# BW1098OBC_Connector.net
KiCad netlist of a schematic drawn in Altium Designer
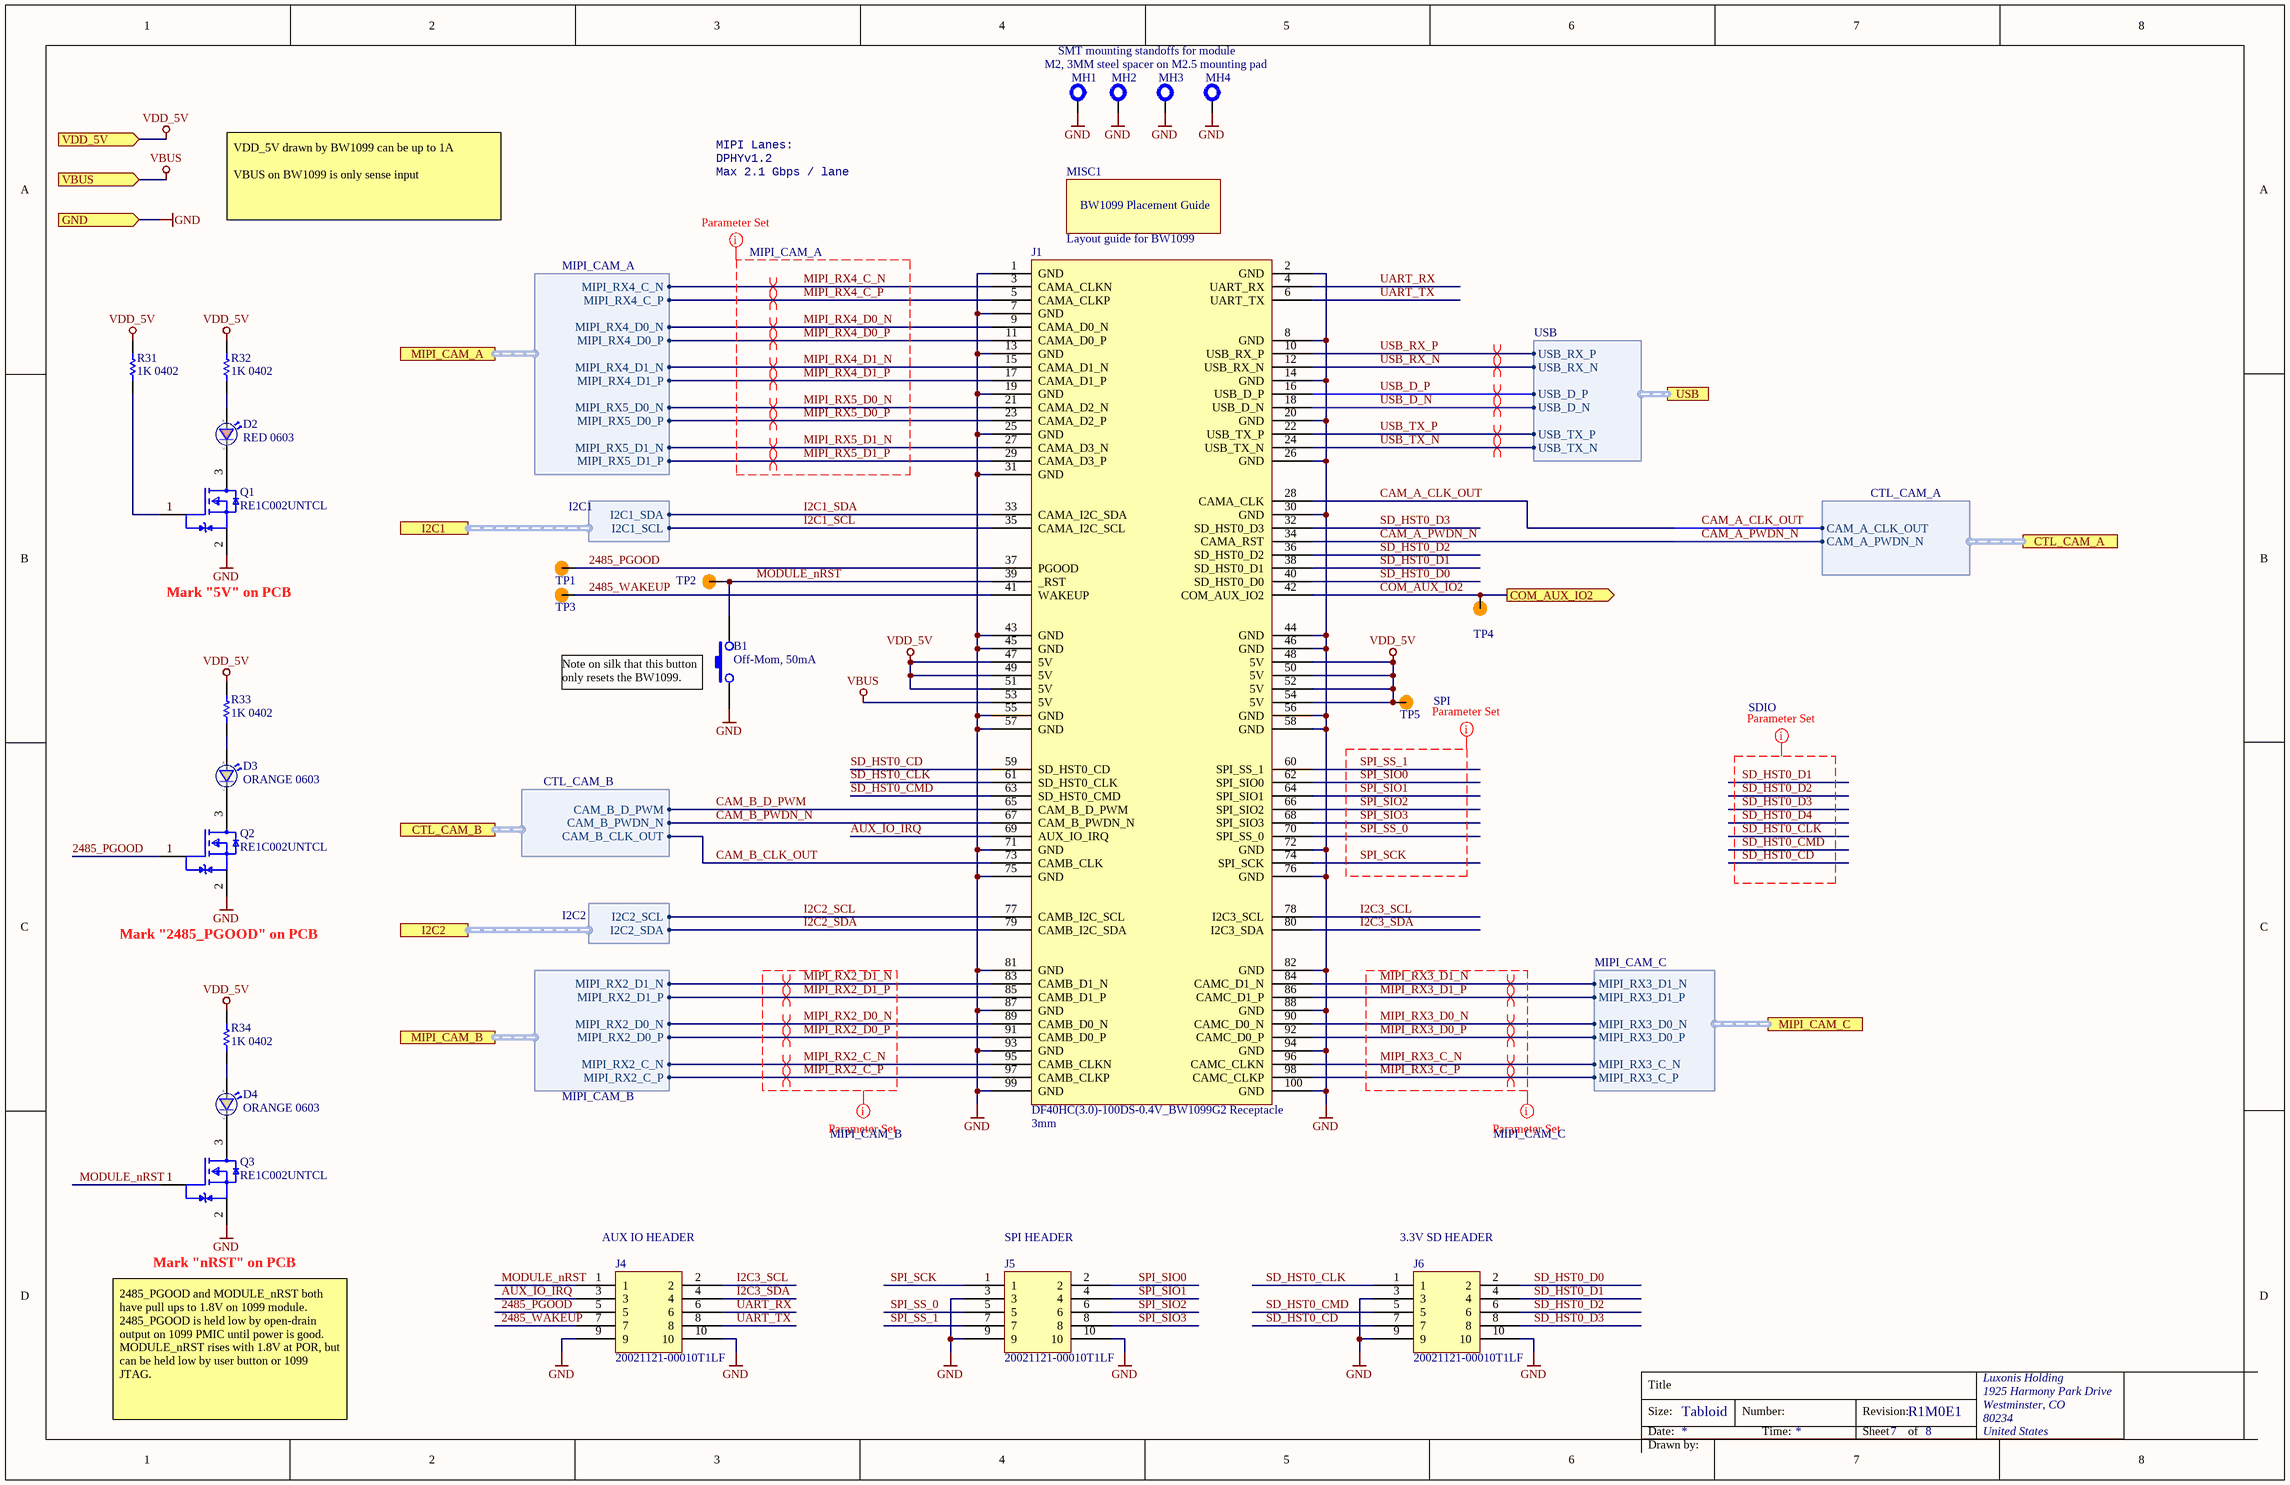
[diagram p0: BW1098OBC_Connector.SchDoc]

(export (version "E")
  (design (tool "Eeschema 10.0.6"))
  (components
    (comp (ref "B1")
      (value "Off-Mom, 50mA")
      (footprint "LuxonisMaster:DTSM-32N-V")
      (description "SWITCH TACTILE SMT 3.5mm * 6mm , brown 160gf")
      (libsource (lib "LuxonisMaster") (part "DTSM-32N-V"))
    )
    (comp (ref "D2")
      (value "RED 0603")
      (footprint "LuxonisMaster:SML_D1xx8W")
      (description "LED RED DIFFUSED 0603 SMD Red 620nm LED Indication - Discrete 2.2V 0603 (1608 Metric)")
      (libsource (lib "LuxonisMaster") (part "SML-D12U8WT86"))
    )
    (comp (ref "D3")
      (value "ORANGE 0603")
      (footprint "LuxonisMaster:SML_D1xx8W")
      (description "LED ORANGE DIFFUSED 0603 SMD Orange 605nm LED Indication - Discrete 2.2V 0603 (1608 Metric)")
      (libsource (lib "LuxonisMaster") (part "SML-D12D8WT86"))
    )
    (comp (ref "D4")
      (value "ORANGE 0603")
      (footprint "LuxonisMaster:SML_D1xx8W")
      (description "LED ORANGE DIFFUSED 0603 SMD Orange 605nm LED Indication - Discrete 2.2V 0603 (1608 Metric)")
      (libsource (lib "LuxonisMaster") (part "SML-D12D8WT86"))
    )
    (comp (ref "J1")
      (value "DF40HC(3.0)-100DS-0.4V_BW1099G2 Receptacle")
      (footprint "LuxonisMaster:DF40HC-3.0-100DS-0.4V_minpad")
      (description "CONN RCPT 100POS 0.4MM SMD GOLD")
      (fields (field (name "MATED STACKING HEIGHT") "3mm"))
      (libsource (lib "LuxonisMaster") (part "DF40HC(3.0)-100DS-0.4V_BW1099_G2"))
    )
    (comp (ref "J4")
      (value "20021121-00010T1LF")
      (footprint "BW1098OBC:20021121-00010T1LF")
      (description "CONN HEADER SMD 10POS 1.27MM")
      (libsource (lib "BW1098OBC") (part "20021121-00010T1LF"))
    )
    (comp (ref "J5")
      (value "20021121-00010T1LF")
      (footprint "BW1098OBC:20021121-00010T1LF")
      (description "CONN HEADER SMD 10POS 1.27MM")
      (libsource (lib "BW1098OBC") (part "20021121-00010T1LF"))
    )
    (comp (ref "J6")
      (value "20021121-00010T1LF")
      (footprint "BW1098OBC:20021121-00010T1LF")
      (description "CONN HEADER SMD 10POS 1.27MM")
      (libsource (lib "BW1098OBC") (part "20021121-00010T1LF"))
    )
    (comp (ref "MH1")
      (value "M2, 3MM steel spacer on M2.5 mounting pad")
      (footprint "LuxonisMaster:9774030243R")
      (description "MP ROUND STANDOFF M2X0.4 STEEL 3MM")
      (libsource (lib "LuxonisMaster") (part "9774030243R"))
    )
    (comp (ref "MH2")
      (value "M2, 3MM steel spacer on M2.5 mounting pad")
      (footprint "LuxonisMaster:9774030243R")
      (description "MP ROUND STANDOFF M2X0.4 STEEL 3MM")
      (libsource (lib "LuxonisMaster") (part "9774030243R"))
    )
    (comp (ref "MH3")
      (value "M2, 3MM steel spacer on M2.5 mounting pad")
      (footprint "LuxonisMaster:9774030243R")
      (description "MP ROUND STANDOFF M2X0.4 STEEL 3MM")
      (libsource (lib "LuxonisMaster") (part "9774030243R"))
    )
    (comp (ref "MH4")
      (value "M2, 3MM steel spacer on M2.5 mounting pad")
      (footprint "LuxonisMaster:9774030243R")
      (description "MP ROUND STANDOFF M2X0.4 STEEL 3MM")
      (libsource (lib "LuxonisMaster") (part "9774030243R"))
    )
    (comp (ref "MISC1")
      (value "Layout guide for BW1099")
      (footprint "LuxonisMaster:BW1099_Footprint")
      (description "MISC - Use for aligning BW1099 mount")
      (libsource (lib "LuxonisMaster") (part "BW1099_Footprint"))
    )
    (comp (ref "Q1")
      (value "RE1C002UNTCL")
      (footprint "LuxonisMaster:RE1C002UNTCL")
      (description "MOSFET N-CH 20V 0.2A EMT3")
      (libsource (lib "LuxonisMaster") (part "RE1C002UNTCL"))
    )
    (comp (ref "Q2")
      (value "RE1C002UNTCL")
      (footprint "LuxonisMaster:RE1C002UNTCL")
      (description "MOSFET N-CH 20V 0.2A EMT3")
      (libsource (lib "LuxonisMaster") (part "RE1C002UNTCL"))
    )
    (comp (ref "Q3")
      (value "RE1C002UNTCL")
      (footprint "LuxonisMaster:RE1C002UNTCL")
      (description "MOSFET N-CH 20V 0.2A EMT3")
      (libsource (lib "LuxonisMaster") (part "RE1C002UNTCL"))
    )
    (comp (ref "R31")
      (value "1K 0402")
      (footprint "RES_Altium_Vault_Generic:RESC0402(1005)_L")
      (fields (field (name "TOLERANCE") "1%"))
      (libsource (lib "LuxonisMaster") (part "RC0402FR-071KL"))
    )
    (comp (ref "R32")
      (value "1K 0402")
      (footprint "RES_Altium_Vault_Generic:RESC0402(1005)_L")
      (fields (field (name "TOLERANCE") "1%"))
      (libsource (lib "LuxonisMaster") (part "RC0402FR-071KL"))
    )
    (comp (ref "R33")
      (value "1K 0402")
      (footprint "RES_Altium_Vault_Generic:RESC0402(1005)_L")
      (fields (field (name "TOLERANCE") "1%"))
      (libsource (lib "LuxonisMaster") (part "RC0402FR-071KL"))
    )
    (comp (ref "R34")
      (value "1K 0402")
      (footprint "RES_Altium_Vault_Generic:RESC0402(1005)_L")
      (fields (field (name "TOLERANCE") "1%"))
      (libsource (lib "LuxonisMaster") (part "RC0402FR-071KL"))
    )
    (comp (ref "TP1")
      (value "TP100_200_NS")
      (footprint "LuxonisMaster:TP100_200_NS")
      (libsource (lib "LuxonisMaster") (part "TEST_POINT"))
    )
    (comp (ref "TP2")
      (value "TP100_200_NS")
      (footprint "LuxonisMaster:TP100_200_NS")
      (libsource (lib "LuxonisMaster") (part "TEST_POINT"))
    )
    (comp (ref "TP3")
      (value "TP100_200_NS")
      (footprint "LuxonisMaster:TP100_200_NS")
      (libsource (lib "LuxonisMaster") (part "TEST_POINT"))
    )
    (comp (ref "TP4")
      (value "TP100_200_NS")
      (footprint "LuxonisMaster:TP100_200_NS")
      (libsource (lib "LuxonisMaster") (part "TEST_POINT"))
    )
    (comp (ref "TP5")
      (value "TP100_200_NS")
      (footprint "LuxonisMaster:TP100_200_NS")
      (libsource (lib "LuxonisMaster") (part "TEST_POINT"))
    )
  )
  (nets
    (net (code "9") (name "/2485_PGOOD") (class "Default")
      (node (ref "J1") (pin "37") (pinfunction "PGOOD_37") (pintype "passive"))
      (node (ref "J4") (pin "5") (pinfunction "5_5") (pintype "passive"))
      (node (ref "Q2") (pin "1") (pinfunction "Gate_1") (pintype "passive"))
      (node (ref "TP1") (pin "1") (pintype "passive"))
    )
    (net (code "10") (name "/2485_WAKEUP") (class "Default")
      (node (ref "J1") (pin "41") (pinfunction "WAKEUP_41") (pintype "passive"))
      (node (ref "J4") (pin "7") (pinfunction "7_7") (pintype "passive"))
      (node (ref "TP3") (pin "1") (pintype "passive"))
    )
    (net (code "11") (name "/AUX_IO_IRQ") (class "Default")
      (node (ref "J1") (pin "69") (pinfunction "AUX_IO_IRQ_69") (pintype "passive"))
      (node (ref "J4") (pin "3") (pinfunction "3_3") (pintype "passive"))
    )
    (net (code "12") (name "/CAM_A_CLK_OUT") (class "Default")
      (node (ref "J1") (pin "28") (pinfunction "CAMA_CLK_28") (pintype "passive"))
    )
    (net (code "13") (name "/CAM_A_PWDN_N") (class "Default")
      (node (ref "J1") (pin "34") (pinfunction "CAMA_RST_34") (pintype "passive"))
    )
    (net (code "14") (name "/CAM_B_CLK_OUT") (class "Default")
      (node (ref "J1") (pin "73") (pinfunction "CAMB_CLK_73") (pintype "passive"))
    )
    (net (code "15") (name "/CAM_B_D_PWM") (class "Default")
      (node (ref "J1") (pin "65") (pinfunction "CAM_B_D_PWM_65") (pintype "passive"))
    )
    (net (code "16") (name "/CAM_B_PWDN_N") (class "Default")
      (node (ref "J1") (pin "67") (pinfunction "CAM_B_PWDN_N_67") (pintype "passive"))
    )
    (net (code "17") (name "/COM_AUX_IO2") (class "Default")
      (node (ref "J1") (pin "42") (pinfunction "COM_AUX_IO2_42") (pintype "passive"))
      (node (ref "TP4") (pin "1") (pintype "passive"))
    )
    (net (code "18") (name "/I2C1_SCL") (class "Default")
      (node (ref "J1") (pin "35") (pinfunction "CAMA_I2C_SCL_35") (pintype "passive"))
    )
    (net (code "19") (name "/I2C1_SDA") (class "Default")
      (node (ref "J1") (pin "33") (pinfunction "CAMA_I2C_SDA_33") (pintype "passive"))
    )
    (net (code "20") (name "/I2C2_SCL") (class "Default")
      (node (ref "J1") (pin "77") (pinfunction "CAMB_I2C_SCL_77") (pintype "passive"))
    )
    (net (code "21") (name "/I2C2_SDA") (class "Default")
      (node (ref "J1") (pin "79") (pinfunction "CAMB_I2C_SDA_79") (pintype "passive"))
    )
    (net (code "22") (name "/I2C3_SCL") (class "Default")
      (node (ref "J1") (pin "78") (pinfunction "I2C3_SCL_78") (pintype "passive"))
      (node (ref "J4") (pin "2") (pinfunction "2_2") (pintype "passive"))
    )
    (net (code "23") (name "/I2C3_SDA") (class "Default")
      (node (ref "J1") (pin "80") (pinfunction "I2C3_SDA_80") (pintype "passive"))
      (node (ref "J4") (pin "4") (pinfunction "4_4") (pintype "passive"))
    )
    (net (code "24") (name "/MIPI_RX2_C_N") (class "Default")
      (node (ref "J1") (pin "95") (pinfunction "CAMB_CLKN_95") (pintype "passive"))
    )
    (net (code "25") (name "/MIPI_RX2_C_P") (class "Default")
      (node (ref "J1") (pin "97") (pinfunction "CAMB_CLKP_97") (pintype "passive"))
    )
    (net (code "26") (name "/MIPI_RX2_D0_N") (class "Default")
      (node (ref "J1") (pin "89") (pinfunction "CAMB_D0_N_89") (pintype "passive"))
    )
    (net (code "27") (name "/MIPI_RX2_D0_P") (class "Default")
      (node (ref "J1") (pin "91") (pinfunction "CAMB_D0_P_91") (pintype "passive"))
    )
    (net (code "28") (name "/MIPI_RX2_D1_N") (class "Default")
      (node (ref "J1") (pin "83") (pinfunction "CAMB_D1_N_83") (pintype "passive"))
    )
    (net (code "29") (name "/MIPI_RX2_D1_P") (class "Default")
      (node (ref "J1") (pin "85") (pinfunction "CAMB_D1_P_85") (pintype "passive"))
    )
    (net (code "30") (name "/MIPI_RX3_C_N") (class "Default")
      (node (ref "J1") (pin "96") (pinfunction "CAMC_CLKN_96") (pintype "passive"))
    )
    (net (code "31") (name "/MIPI_RX3_C_P") (class "Default")
      (node (ref "J1") (pin "98") (pinfunction "CAMC_CLKP_98") (pintype "passive"))
    )
    (net (code "32") (name "/MIPI_RX3_D0_N") (class "Default")
      (node (ref "J1") (pin "90") (pinfunction "CAMC_D0_N_90") (pintype "passive"))
    )
    (net (code "33") (name "/MIPI_RX3_D0_P") (class "Default")
      (node (ref "J1") (pin "92") (pinfunction "CAMC_D0_P_92") (pintype "passive"))
    )
    (net (code "34") (name "/MIPI_RX3_D1_N") (class "Default")
      (node (ref "J1") (pin "84") (pinfunction "CAMC_D1_N_84") (pintype "passive"))
    )
    (net (code "35") (name "/MIPI_RX3_D1_P") (class "Default")
      (node (ref "J1") (pin "86") (pinfunction "CAMC_D1_P_86") (pintype "passive"))
    )
    (net (code "36") (name "/MIPI_RX4_C_N") (class "Default")
      (node (ref "J1") (pin "3") (pinfunction "CAMA_CLKN_3") (pintype "passive"))
    )
    (net (code "37") (name "/MIPI_RX4_C_P") (class "Default")
      (node (ref "J1") (pin "5") (pinfunction "CAMA_CLKP_5") (pintype "passive"))
    )
    (net (code "38") (name "/MIPI_RX4_D0_N") (class "Default")
      (node (ref "J1") (pin "9") (pinfunction "CAMA_D0_N_9") (pintype "passive"))
    )
    (net (code "39") (name "/MIPI_RX4_D0_P") (class "Default")
      (node (ref "J1") (pin "11") (pinfunction "CAMA_D0_P_11") (pintype "passive"))
    )
    (net (code "40") (name "/MIPI_RX4_D1_N") (class "Default")
      (node (ref "J1") (pin "15") (pinfunction "CAMA_D1_N_15") (pintype "passive"))
    )
    (net (code "41") (name "/MIPI_RX4_D1_P") (class "Default")
      (node (ref "J1") (pin "17") (pinfunction "CAMA_D1_P_17") (pintype "passive"))
    )
    (net (code "42") (name "/MIPI_RX5_D0_N") (class "Default")
      (node (ref "J1") (pin "21") (pinfunction "CAMA_D2_N_21") (pintype "passive"))
    )
    (net (code "43") (name "/MIPI_RX5_D0_P") (class "Default")
      (node (ref "J1") (pin "23") (pinfunction "CAMA_D2_P_23") (pintype "passive"))
    )
    (net (code "44") (name "/MIPI_RX5_D1_N") (class "Default")
      (node (ref "J1") (pin "27") (pinfunction "CAMA_D3_N_27") (pintype "passive"))
    )
    (net (code "45") (name "/MIPI_RX5_D1_P") (class "Default")
      (node (ref "J1") (pin "29") (pinfunction "CAMA_D3_P_29") (pintype "passive"))
    )
    (net (code "46") (name "/MODULE_nRST") (class "Default")
      (node (ref "B1") (pin "2") (pinfunction "2_2") (pintype "passive"))
      (node (ref "J1") (pin "39") (pinfunction "_RST_39") (pintype "passive"))
      (node (ref "J4") (pin "1") (pinfunction "1_1") (pintype "passive"))
      (node (ref "Q3") (pin "1") (pinfunction "Gate_1") (pintype "passive"))
      (node (ref "TP2") (pin "1") (pintype "passive"))
    )
    (net (code "47") (name "/SD_HST0_CD") (class "Default")
      (node (ref "J1") (pin "59") (pinfunction "SD_HST0_CD_59") (pintype "passive"))
      (node (ref "J6") (pin "7") (pinfunction "7_7") (pintype "passive"))
    )
    (net (code "48") (name "/SD_HST0_CLK") (class "Default")
      (node (ref "J1") (pin "61") (pinfunction "SD_HST0_CLK_61") (pintype "passive"))
      (node (ref "J6") (pin "1") (pinfunction "1_1") (pintype "passive"))
    )
    (net (code "49") (name "/SD_HST0_CMD") (class "Default")
      (node (ref "J1") (pin "63") (pinfunction "SD_HST0_CMD_63") (pintype "passive"))
      (node (ref "J6") (pin "5") (pinfunction "5_5") (pintype "passive"))
    )
    (net (code "50") (name "/SD_HST0_D0") (class "Default")
      (node (ref "J1") (pin "40") (pinfunction "SD_HST0_D0_40") (pintype "passive"))
      (node (ref "J6") (pin "2") (pinfunction "2_2") (pintype "passive"))
    )
    (net (code "51") (name "/SD_HST0_D1") (class "Default")
      (node (ref "J1") (pin "38") (pinfunction "SD_HST0_D1_38") (pintype "passive"))
      (node (ref "J6") (pin "4") (pinfunction "4_4") (pintype "passive"))
    )
    (net (code "52") (name "/SD_HST0_D2") (class "Default")
      (node (ref "J1") (pin "36") (pinfunction "SD_HST0_D2_36") (pintype "passive"))
      (node (ref "J6") (pin "6") (pinfunction "6_6") (pintype "passive"))
    )
    (net (code "53") (name "/SD_HST0_D3") (class "Default")
      (node (ref "J1") (pin "32") (pinfunction "SD_HST0_D3_32") (pintype "passive"))
      (node (ref "J6") (pin "8") (pinfunction "8_8") (pintype "passive"))
    )
    (net (code "55") (name "/SPI_SCK") (class "Default")
      (node (ref "J1") (pin "74") (pinfunction "SPI_SCK_74") (pintype "passive"))
      (node (ref "J5") (pin "1") (pinfunction "1_1") (pintype "passive"))
    )
    (net (code "56") (name "/SPI_SIO0") (class "Default")
      (node (ref "J1") (pin "62") (pinfunction "SPI_SIO0_62") (pintype "passive"))
      (node (ref "J5") (pin "2") (pinfunction "2_2") (pintype "passive"))
    )
    (net (code "57") (name "/SPI_SIO1") (class "Default")
      (node (ref "J1") (pin "64") (pinfunction "SPI_SIO1_64") (pintype "passive"))
      (node (ref "J5") (pin "4") (pinfunction "4_4") (pintype "passive"))
    )
    (net (code "58") (name "/SPI_SIO2") (class "Default")
      (node (ref "J1") (pin "66") (pinfunction "SPI_SIO2_66") (pintype "passive"))
      (node (ref "J5") (pin "6") (pinfunction "6_6") (pintype "passive"))
    )
    (net (code "59") (name "/SPI_SIO3") (class "Default")
      (node (ref "J1") (pin "68") (pinfunction "SPI_SIO3_68") (pintype "passive"))
      (node (ref "J5") (pin "8") (pinfunction "8_8") (pintype "passive"))
    )
    (net (code "60") (name "/SPI_SS_0") (class "Default")
      (node (ref "J1") (pin "70") (pinfunction "SPI_SS_0_70") (pintype "passive"))
      (node (ref "J5") (pin "5") (pinfunction "5_5") (pintype "passive"))
    )
    (net (code "61") (name "/SPI_SS_1") (class "Default")
      (node (ref "J1") (pin "60") (pinfunction "SPI_SS_1_60") (pintype "passive"))
      (node (ref "J5") (pin "7") (pinfunction "7_7") (pintype "passive"))
    )
    (net (code "62") (name "/UART_RX") (class "Default")
      (node (ref "J1") (pin "4") (pinfunction "UART_RX_4") (pintype "passive"))
      (node (ref "J4") (pin "6") (pinfunction "6_6") (pintype "passive"))
    )
    (net (code "63") (name "/UART_TX") (class "Default")
      (node (ref "J1") (pin "6") (pinfunction "UART_TX_6") (pintype "passive"))
      (node (ref "J4") (pin "8") (pinfunction "8_8") (pintype "passive"))
    )
    (net (code "64") (name "/USB_D_N") (class "Default")
      (node (ref "J1") (pin "18") (pinfunction "USB_D_N_18") (pintype "passive"))
    )
    (net (code "65") (name "/USB_D_P") (class "Default")
      (node (ref "J1") (pin "16") (pinfunction "USB_D_P_16") (pintype "passive"))
    )
    (net (code "66") (name "/USB_RX_N") (class "Default")
      (node (ref "J1") (pin "12") (pinfunction "USB_RX_N_12") (pintype "passive"))
    )
    (net (code "67") (name "/USB_RX_P") (class "Default")
      (node (ref "J1") (pin "10") (pinfunction "USB_RX_P_10") (pintype "passive"))
    )
    (net (code "68") (name "/USB_TX_N") (class "Default")
      (node (ref "J1") (pin "24") (pinfunction "USB_TX_N_24") (pintype "passive"))
    )
    (net (code "69") (name "/USB_TX_P") (class "Default")
      (node (ref "J1") (pin "22") (pinfunction "USB_TX_P_22") (pintype "passive"))
    )
    (net (code "78") (name "GND") (class "Default")
      (node (ref "B1") (pin "1") (pinfunction "1_1") (pintype "passive"))
      (node (ref "J1") (pin "1") (pinfunction "GND_1") (pintype "passive"))
      (node (ref "J1") (pin "100") (pinfunction "GND_100") (pintype "passive"))
      (node (ref "J1") (pin "13") (pinfunction "GND_13") (pintype "passive"))
      (node (ref "J1") (pin "14") (pinfunction "GND_14") (pintype "passive"))
      (node (ref "J1") (pin "19") (pinfunction "GND_19") (pintype "passive"))
      (node (ref "J1") (pin "2") (pinfunction "GND_2") (pintype "passive"))
      (node (ref "J1") (pin "20") (pinfunction "GND_20") (pintype "passive"))
      (node (ref "J1") (pin "25") (pinfunction "GND_25") (pintype "passive"))
      (node (ref "J1") (pin "26") (pinfunction "GND_26") (pintype "passive"))
      (node (ref "J1") (pin "30") (pinfunction "GND_30") (pintype "passive"))
      (node (ref "J1") (pin "31") (pinfunction "GND_31") (pintype "passive"))
      (node (ref "J1") (pin "43") (pinfunction "GND_43") (pintype "passive"))
      (node (ref "J1") (pin "44") (pinfunction "GND_44") (pintype "passive"))
      (node (ref "J1") (pin "45") (pinfunction "GND_45") (pintype "passive"))
      (node (ref "J1") (pin "46") (pinfunction "GND_46") (pintype "passive"))
      (node (ref "J1") (pin "55") (pinfunction "GND_55") (pintype "passive"))
      (node (ref "J1") (pin "56") (pinfunction "GND_56") (pintype "passive"))
      (node (ref "J1") (pin "57") (pinfunction "GND_57") (pintype "passive"))
      (node (ref "J1") (pin "58") (pinfunction "GND_58") (pintype "passive"))
      (node (ref "J1") (pin "7") (pinfunction "GND_7") (pintype "passive"))
      (node (ref "J1") (pin "71") (pinfunction "GND_71") (pintype "passive"))
      (node (ref "J1") (pin "72") (pinfunction "GND_72") (pintype "passive"))
      (node (ref "J1") (pin "75") (pinfunction "GND_75") (pintype "passive"))
      (node (ref "J1") (pin "76") (pinfunction "GND_76") (pintype "passive"))
      (node (ref "J1") (pin "8") (pinfunction "GND_8") (pintype "passive"))
      (node (ref "J1") (pin "81") (pinfunction "GND_81") (pintype "passive"))
      (node (ref "J1") (pin "82") (pinfunction "GND_82") (pintype "passive"))
      (node (ref "J1") (pin "87") (pinfunction "GND_87") (pintype "passive"))
      (node (ref "J1") (pin "88") (pinfunction "GND_88") (pintype "passive"))
      (node (ref "J1") (pin "93") (pinfunction "GND_93") (pintype "passive"))
      (node (ref "J1") (pin "94") (pinfunction "GND_94") (pintype "passive"))
      (node (ref "J1") (pin "99") (pinfunction "GND_99") (pintype "passive"))
      (node (ref "J4") (pin "10") (pinfunction "10_10") (pintype "passive"))
      (node (ref "J4") (pin "9") (pinfunction "9_9") (pintype "passive"))
      (node (ref "J5") (pin "10") (pinfunction "10_10") (pintype "passive"))
      (node (ref "J5") (pin "3") (pinfunction "3_3") (pintype "passive"))
      (node (ref "J5") (pin "9") (pinfunction "9_9") (pintype "passive"))
      (node (ref "J6") (pin "10") (pinfunction "10_10") (pintype "passive"))
      (node (ref "J6") (pin "3") (pinfunction "3_3") (pintype "passive"))
      (node (ref "J6") (pin "9") (pinfunction "9_9") (pintype "passive"))
      (node (ref "MH1") (pin "1") (pintype "passive"))
      (node (ref "MH2") (pin "1") (pintype "passive"))
      (node (ref "MH3") (pin "1") (pintype "passive"))
      (node (ref "MH4") (pin "1") (pintype "passive"))
      (node (ref "Q1") (pin "2") (pinfunction "Source_2") (pintype "passive"))
      (node (ref "Q2") (pin "2") (pinfunction "Source_2") (pintype "passive"))
      (node (ref "Q3") (pin "2") (pinfunction "Source_2") (pintype "passive"))
    )
    (net (code "79") (name "Net-(D2-A)") (class "Default")
      (node (ref "D2") (pin "2") (pinfunction "A_2") (pintype "passive"))
      (node (ref "R32") (pin "1") (pinfunction "1_1") (pintype "passive"))
    )
    (net (code "80") (name "Net-(D2-C)") (class "Default")
      (node (ref "D2") (pin "1") (pinfunction "C_1") (pintype "passive"))
      (node (ref "Q1") (pin "3") (pinfunction "Drain_3") (pintype "passive"))
    )
    (net (code "81") (name "Net-(D3-A)") (class "Default")
      (node (ref "D3") (pin "2") (pinfunction "A_2") (pintype "passive"))
      (node (ref "R33") (pin "1") (pinfunction "1_1") (pintype "passive"))
    )
    (net (code "82") (name "Net-(D3-C)") (class "Default")
      (node (ref "D3") (pin "1") (pinfunction "C_1") (pintype "passive"))
      (node (ref "Q2") (pin "3") (pinfunction "Drain_3") (pintype "passive"))
    )
    (net (code "83") (name "Net-(D4-A)") (class "Default")
      (node (ref "D4") (pin "2") (pinfunction "A_2") (pintype "passive"))
      (node (ref "R34") (pin "1") (pinfunction "1_1") (pintype "passive"))
    )
    (net (code "84") (name "Net-(D4-C)") (class "Default")
      (node (ref "D4") (pin "1") (pinfunction "C_1") (pintype "passive"))
      (node (ref "Q3") (pin "3") (pinfunction "Drain_3") (pintype "passive"))
    )
    (net (code "85") (name "Net-(Q1-Gate)") (class "Default")
      (node (ref "Q1") (pin "1") (pinfunction "Gate_1") (pintype "passive"))
      (node (ref "R31") (pin "1") (pinfunction "1_1") (pintype "passive"))
    )
    (net (code "86") (name "VBUS") (class "Default")
      (node (ref "J1") (pin "53") (pinfunction "5V_53") (pintype "passive"))
    )
    (net (code "87") (name "VDD_5V") (class "Default")
      (node (ref "J1") (pin "47") (pinfunction "5V_47") (pintype "passive"))
      (node (ref "J1") (pin "48") (pinfunction "5V_48") (pintype "passive"))
      (node (ref "J1") (pin "49") (pinfunction "5V_49") (pintype "passive"))
      (node (ref "J1") (pin "50") (pinfunction "5V_50") (pintype "passive"))
      (node (ref "J1") (pin "51") (pinfunction "5V_51") (pintype "passive"))
      (node (ref "J1") (pin "52") (pinfunction "5V_52") (pintype "passive"))
      (node (ref "J1") (pin "54") (pinfunction "5V_54") (pintype "passive"))
      (node (ref "R31") (pin "2") (pinfunction "2_2") (pintype "passive"))
      (node (ref "R32") (pin "2") (pinfunction "2_2") (pintype "passive"))
      (node (ref "R33") (pin "2") (pinfunction "2_2") (pintype "passive"))
      (node (ref "R34") (pin "2") (pinfunction "2_2") (pintype "passive"))
      (node (ref "TP5") (pin "1") (pintype "passive"))
    )
  )
)
